# Analog_Temp_Ctrl.net
KiCad netlist of a schematic drawn in EAGLE
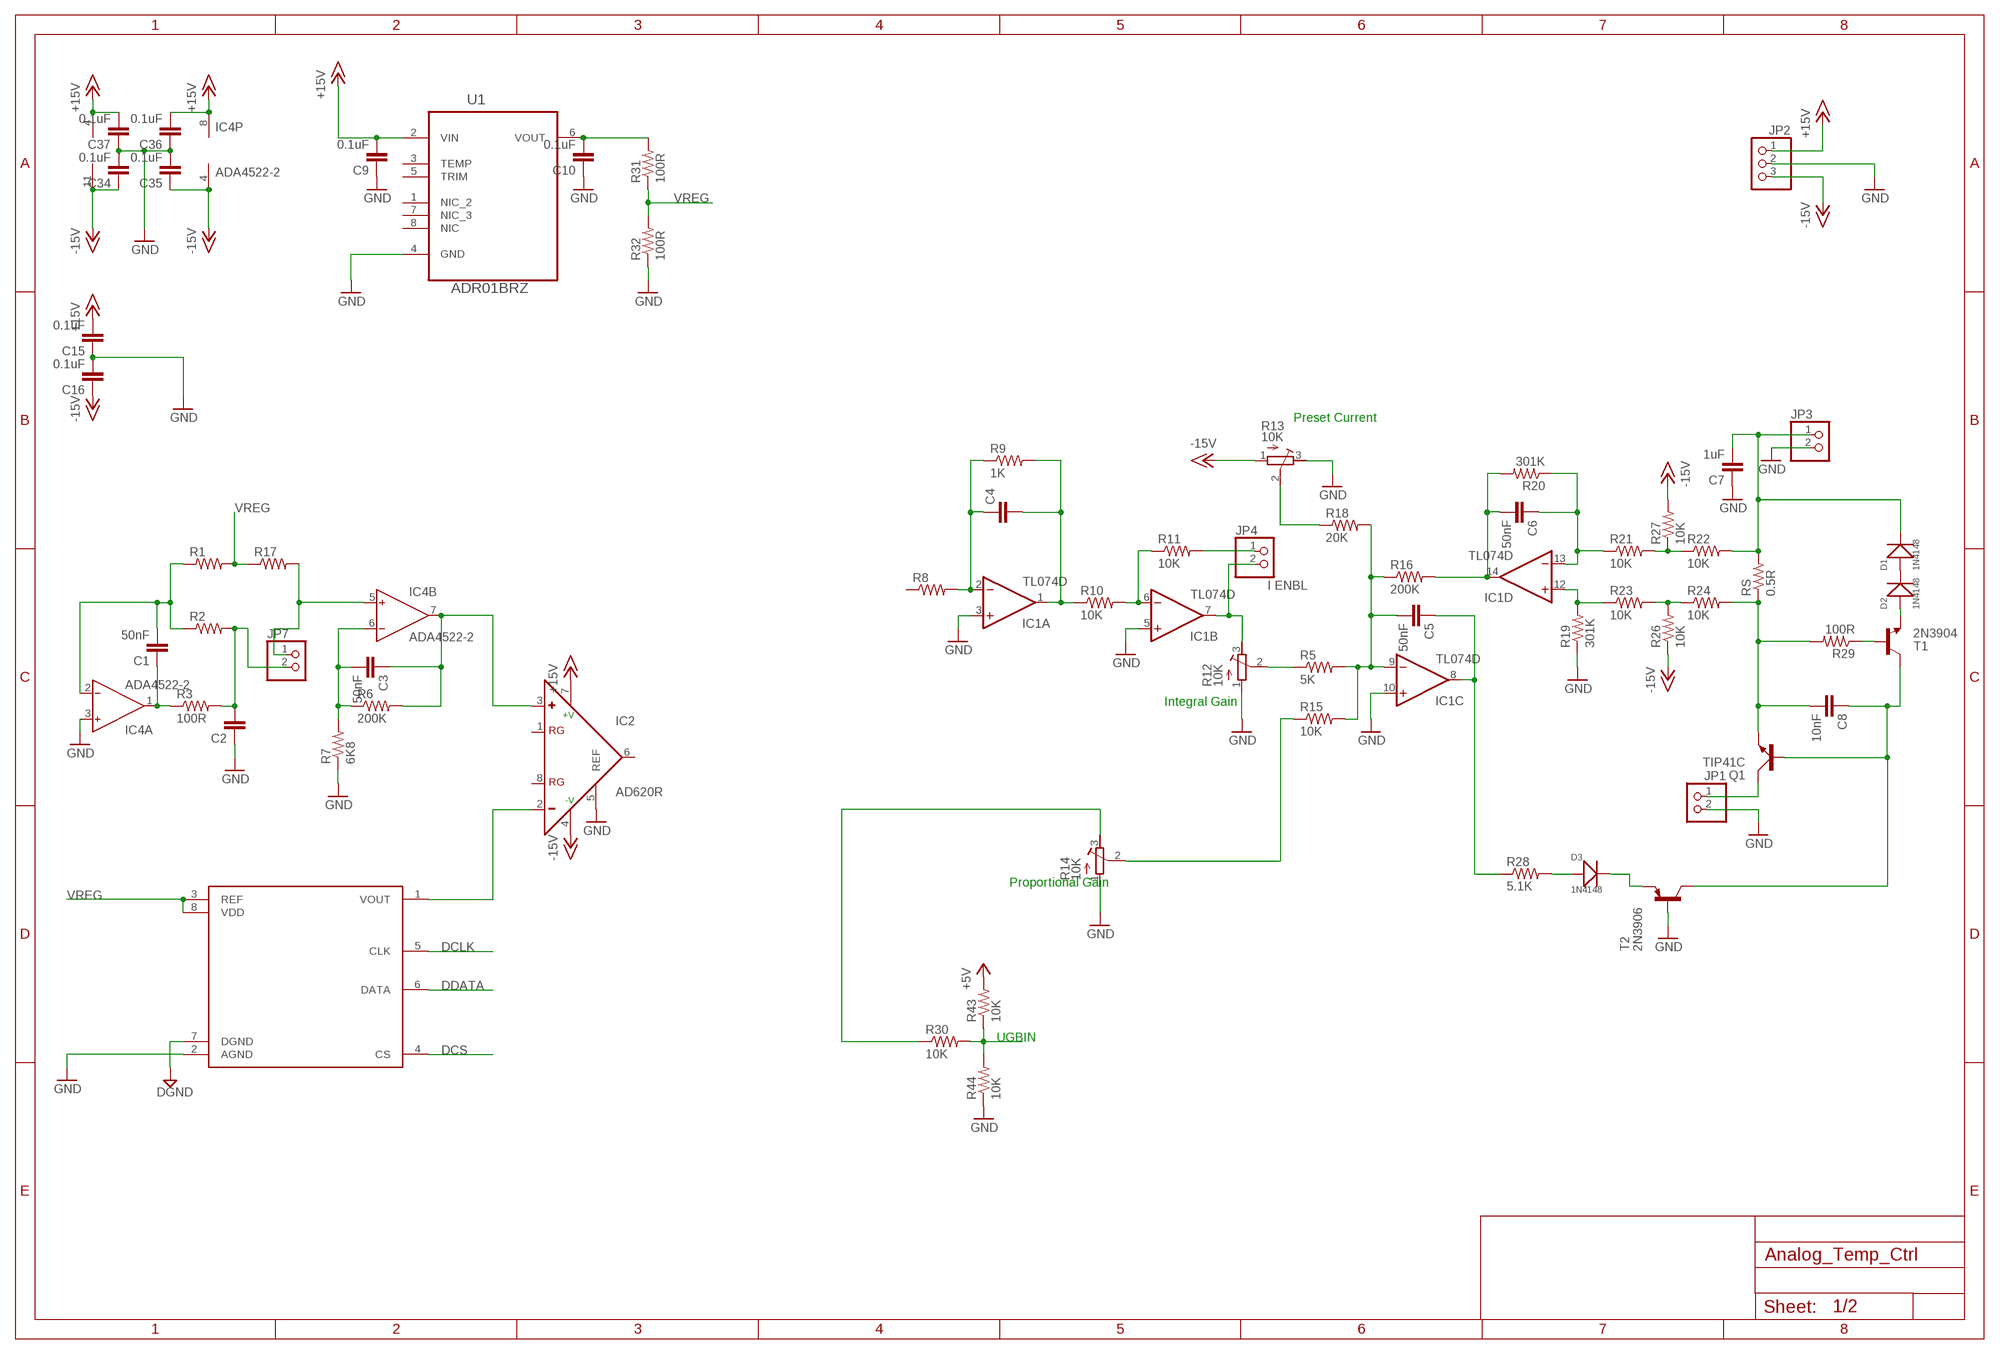
[diagram p0: schematic, sheet 1]
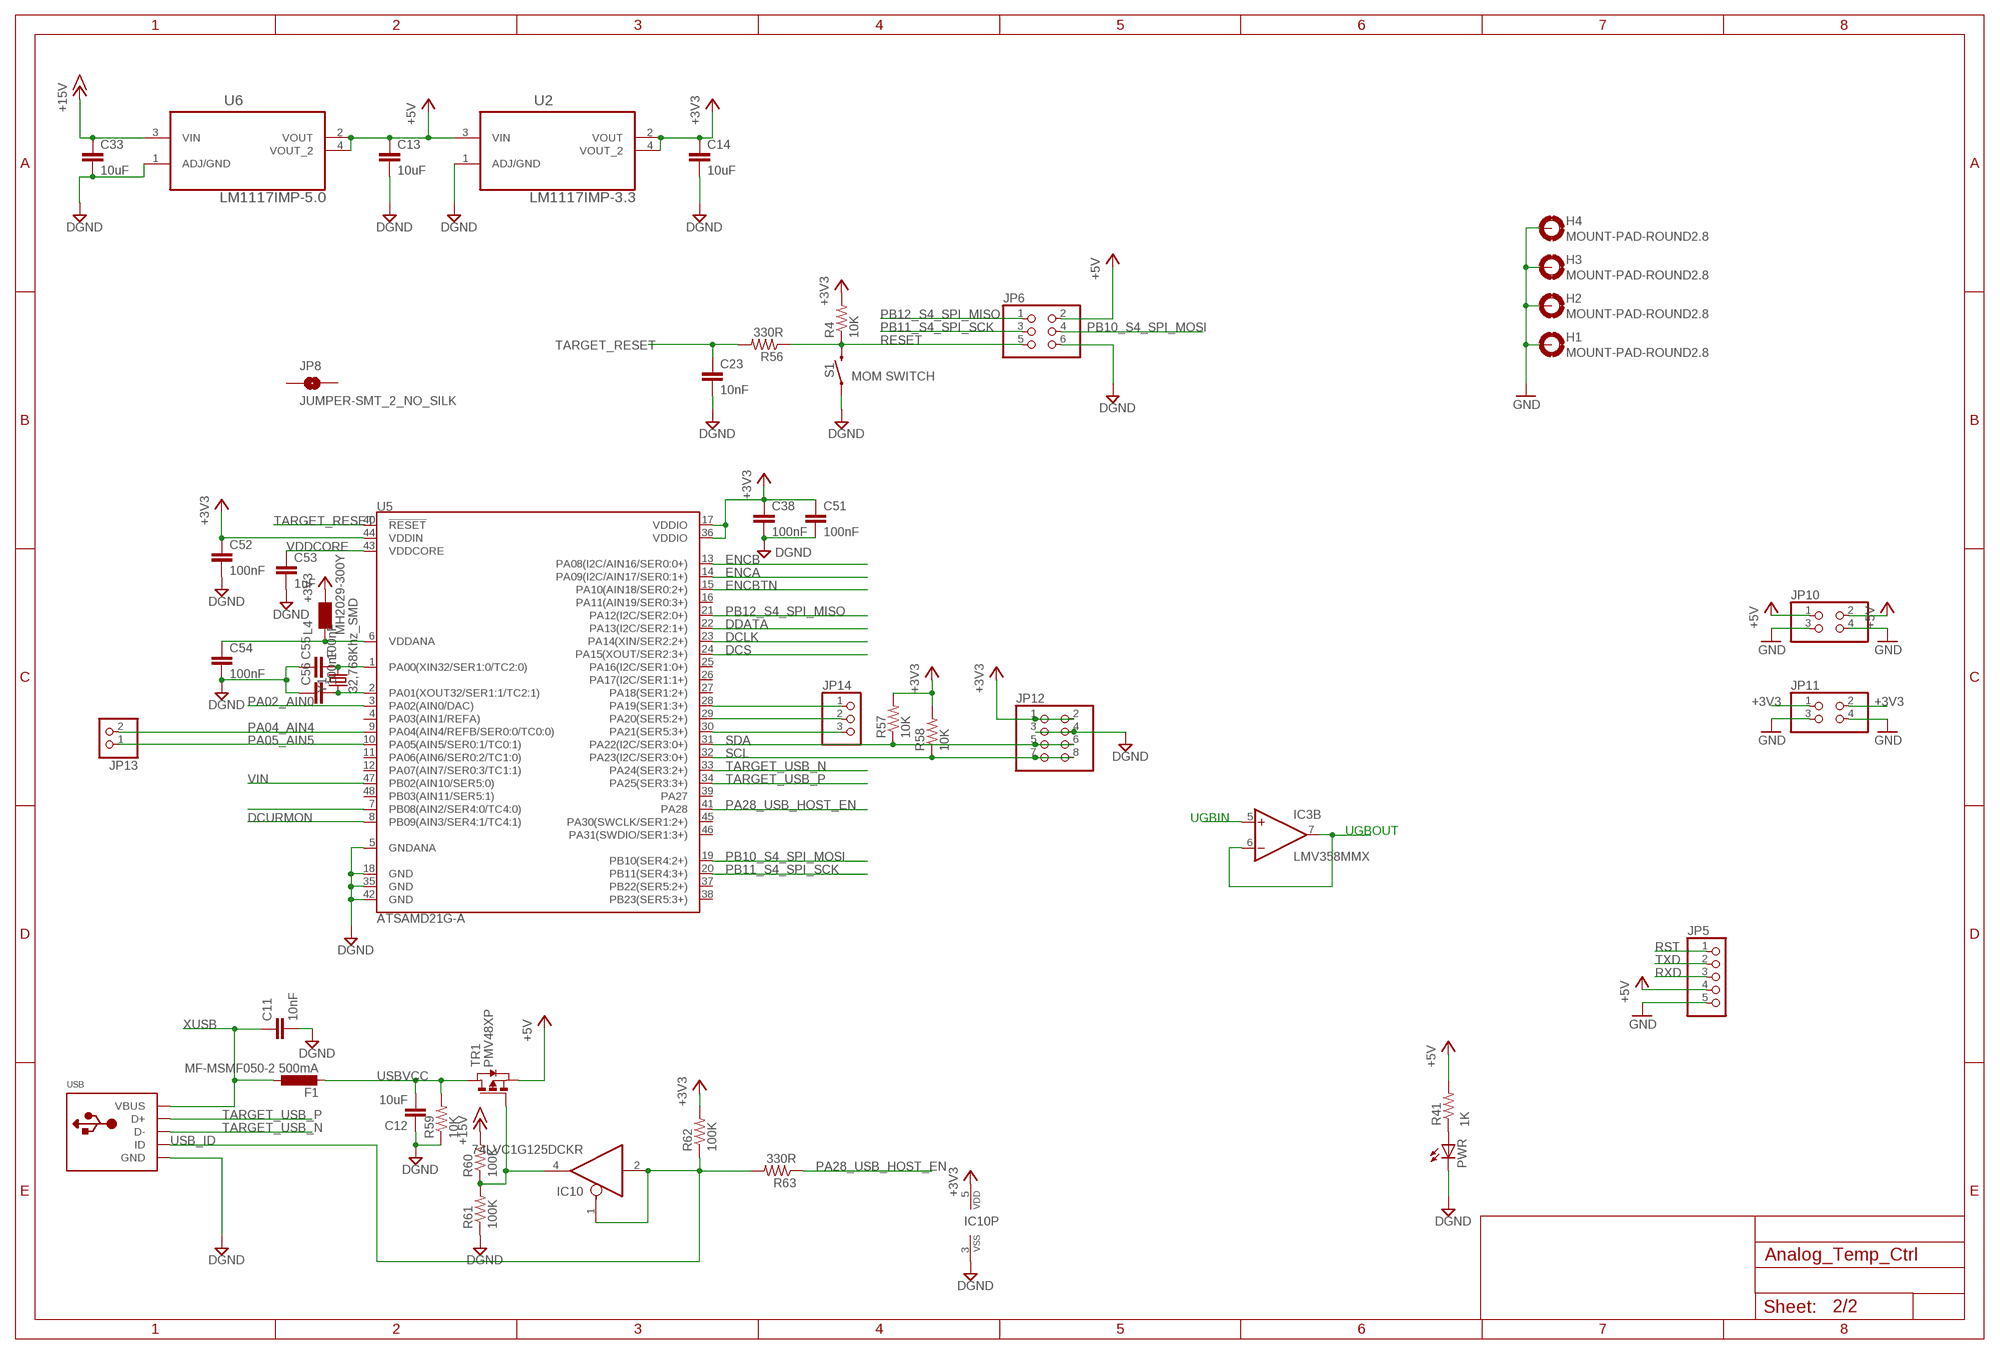
[diagram p1: schematic, sheet 2]

(export (version "E")
  (design (tool "Eeschema 10.0.6"))
  (components
    (comp (ref "C11")
      (value "10nF")
      (footprint "eagle-import:C0805")
      (libsource (lib "eagle-import") (part "C-EUC0805"))
    )
    (comp (ref "C12")
      (value "10uF")
      (footprint "eagle-import:C0805")
      (libsource (lib "eagle-import") (part "C-EUC0805"))
    )
    (comp (ref "C13")
      (value "10uF")
      (footprint "eagle-import:C0805")
      (libsource (lib "eagle-import") (part "C-EUC0805"))
    )
    (comp (ref "C14")
      (value "10uF")
      (footprint "eagle-import:C0805")
      (libsource (lib "eagle-import") (part "C-EUC0805"))
    )
    (comp (ref "C23")
      (value "10nF")
      (footprint "eagle-import:C0805")
      (libsource (lib "eagle-import") (part "C-EUC0805"))
    )
    (comp (ref "C33")
      (value "10uF")
      (footprint "eagle-import:C0805")
      (libsource (lib "eagle-import") (part "C-EUC0805"))
    )
    (comp (ref "C38")
      (value "100nF")
      (footprint "eagle-import:C0805")
      (libsource (lib "eagle-import") (part "C-EUC0805"))
    )
    (comp (ref "C51")
      (value "100nF")
      (footprint "eagle-import:C0805")
      (libsource (lib "eagle-import") (part "C-EUC0805"))
    )
    (comp (ref "C52")
      (value "100nF")
      (footprint "eagle-import:C0805")
      (libsource (lib "eagle-import") (part "C-EUC0805"))
    )
    (comp (ref "C53")
      (value "1uF")
      (footprint "eagle-import:C0805")
      (libsource (lib "eagle-import") (part "C-EUC0805"))
    )
    (comp (ref "C54")
      (value "100nF")
      (footprint "eagle-import:C0805")
      (libsource (lib "eagle-import") (part "C-EUC0805"))
    )
    (comp (ref "C55")
      (value "100nF")
      (footprint "eagle-import:C0805")
      (libsource (lib "eagle-import") (part "C-EUC0805"))
    )
    (comp (ref "C56")
      (value "100nF")
      (footprint "eagle-import:C0805")
      (libsource (lib "eagle-import") (part "C-EUC0805"))
    )
    (comp (ref "F1")
      (value "MF-MSMF050-2 500mA")
      (footprint "eagle-import:PROTEZIONE_L1812")
      (fields (field (name "PART_NUMBER") "MF-MSMF050-2"))
      (libsource (lib "eagle-import") (part "PROTEZIONE_0002_MF-MSMF050-2"))
    )
    (comp (ref "H1")
      (value "MOUNT-PAD-ROUND2.8")
      (footprint "eagle-import:2,8-PAD")
      (libsource (lib "eagle-import") (part "MOUNT-PAD-ROUND2.8"))
    )
    (comp (ref "H2")
      (value "MOUNT-PAD-ROUND2.8")
      (footprint "eagle-import:2,8-PAD")
      (libsource (lib "eagle-import") (part "MOUNT-PAD-ROUND2.8"))
    )
    (comp (ref "H3")
      (value "MOUNT-PAD-ROUND2.8")
      (footprint "eagle-import:2,8-PAD")
      (libsource (lib "eagle-import") (part "MOUNT-PAD-ROUND2.8"))
    )
    (comp (ref "H4")
      (value "MOUNT-PAD-ROUND2.8")
      (footprint "eagle-import:2,8-PAD")
      (libsource (lib "eagle-import") (part "MOUNT-PAD-ROUND2.8"))
    )
    (comp (ref "IC3")
      (value "LMV358MMX")
      (footprint "eagle-import:MSOP08")
      (libsource (lib "eagle-import") (part "LMV358?MMX"))
    )
    (comp (ref "IC10")
      (value "74LVC1G125DCKR")
      (footprint "eagle-import:INTEGRATEDCIRCUITS_SC70-5")
      (fields (field (name "PART_NUMBER") "SN74LVC1G125DCKR"))
      (libsource (lib "eagle-import") (part "INTEGRATEDCIRCUITS_0040_SN74LVC1G125DCKR"))
    )
    (comp (ref "JP5")
      (value "PINHD-1X5")
      (footprint "eagle-import:1X05")
      (libsource (lib "eagle-import") (part "PINHD-1X5"))
    )
    (comp (ref "JP6")
      (value "PINHD-2X3")
      (footprint "eagle-import:2X03")
      (libsource (lib "eagle-import") (part "PINHD-2X3"))
    )
    (comp (ref "JP8")
      (value "JUMPER-SMT_2_NO_SILK")
      (footprint "eagle-import:SMT-JUMPER_2_NO_SILK")
      (libsource (lib "eagle-import") (part "JUMPER-SMT_2_NO_SILK"))
    )
    (comp (ref "JP10")
      (value "PINHD-2X2")
      (footprint "eagle-import:2X02")
      (libsource (lib "eagle-import") (part "PINHD-2X2"))
    )
    (comp (ref "JP11")
      (value "PINHD-2X2")
      (footprint "eagle-import:2X02")
      (libsource (lib "eagle-import") (part "PINHD-2X2"))
    )
    (comp (ref "JP12")
      (value "PINHD-2X4")
      (footprint "eagle-import:2X04")
      (libsource (lib "eagle-import") (part "PINHD-2X4"))
    )
    (comp (ref "JP13")
      (value "PINHD-1X2")
      (footprint "eagle-import:1X02")
      (libsource (lib "eagle-import") (part "PINHD-1X2"))
    )
    (comp (ref "JP14")
      (value "PINHD-1X3")
      (footprint "eagle-import:1X03")
      (libsource (lib "eagle-import") (part "PINHD-1X3"))
    )
    (comp (ref "L4")
      (value "MH2029-300Y")
      (footprint "eagle-import:PROTEZIONE_0805")
      (fields (field (name "PART_NUMBER") "BLM21PG300SN1D_/_MH2029-300Y"))
      (libsource (lib "eagle-import") (part "PROTEZIONE_0001_BLM21PG300SN1D_/_MH2029-300Y"))
    )
    (comp (ref "PWR")
      (value "LEDCHIPLED_0805")
      (footprint "eagle-import:CHIPLED_0805")
      (libsource (lib "eagle-import") (part "LEDCHIPLED_0805"))
    )
    (comp (ref "R4")
      (value "10K")
      (footprint "eagle-import:R0805")
      (libsource (lib "eagle-import") (part "rcl_334_R-US_R0805"))
    )
    (comp (ref "R41")
      (value "1K")
      (footprint "eagle-import:R0805")
      (libsource (lib "eagle-import") (part "rcl_334_R-US_R0805"))
    )
    (comp (ref "R56")
      (value "330R")
      (footprint "eagle-import:R0805")
      (libsource (lib "eagle-import") (part "rcl_334_R-US_R0805"))
    )
    (comp (ref "R57")
      (value "10K")
      (footprint "eagle-import:R0805")
      (libsource (lib "eagle-import") (part "rcl_334_R-US_R0805"))
    )
    (comp (ref "R58")
      (value "10K")
      (footprint "eagle-import:R0805")
      (libsource (lib "eagle-import") (part "rcl_334_R-US_R0805"))
    )
    (comp (ref "R59")
      (value "10K")
      (footprint "eagle-import:R0805")
      (libsource (lib "eagle-import") (part "rcl_334_R-US_R0805"))
    )
    (comp (ref "R60")
      (value "100K")
      (footprint "eagle-import:R0805")
      (libsource (lib "eagle-import") (part "rcl_334_R-US_R0805"))
    )
    (comp (ref "R61")
      (value "100K")
      (footprint "eagle-import:R0805")
      (libsource (lib "eagle-import") (part "rcl_334_R-US_R0805"))
    )
    (comp (ref "R62")
      (value "100K")
      (footprint "eagle-import:R0805")
      (libsource (lib "eagle-import") (part "rcl_334_R-US_R0805"))
    )
    (comp (ref "R63")
      (value "330R")
      (footprint "eagle-import:R0805")
      (libsource (lib "eagle-import") (part "rcl_334_R-US_R0805"))
    )
    (comp (ref "S1")
      (value "MOM SWITCH")
      (footprint "eagle-import:TACTILE_SWITCH_SMD_5.2MM")
      (libsource (lib "eagle-import") (part "MOMENTARY-SWITCH-SPST-SMD-5.2MM"))
    )
    (comp (ref "TR1")
      (value "PMV48XP")
      (footprint "eagle-import:TRANSISTORS_SOT-23")
      (libsource (lib "eagle-import") (part "TRANSISTORS_0297_PMV48XP"))
    )
    (comp (ref "U2")
      (value "LM1117IMP-3.3")
      (footprint "eagle-import:SOT230P696X180-4N")
      (libsource (lib "eagle-import") (part "LM1117IMP-3.3"))
    )
    (comp (ref "U5")
      (value "ATSAMD21G-A")
      (footprint "eagle-import:TQFP-48")
      (libsource (lib "eagle-import") (part "ATSAMD21G-A"))
    )
    (comp (ref "U6")
      (value "LM1117IMP-5.0")
      (footprint "eagle-import:SOT230P696X180-4N")
      (libsource (lib "eagle-import") (part "LM1117IMP-5.0"))
    )
    (comp (ref "USB")
      (value "USBMINIB")
      (footprint "eagle-import:USB-MINIB")
      (libsource (lib "eagle-import") (part "USBMINIB"))
    )
    (comp (ref "Y1")
      (value "32,768Khz_SMD")
      (footprint "eagle-import:CRISTALLI_RESONATOR_EPSON_FC_145")
      (fields (field (name "PART_NUMBER") "ABS07-32.768KHZ-T"))
      (libsource (lib "eagle-import") (part "CRISTALLI_0213_ABS07-32.768KHZ-T"))
    )
    (comp (ref "C1")
      (value "50nF")
      (footprint "eagle-import:C0805")
      (libsource (lib "eagle-import") (part "C-EUC0805"))
    )
    (comp (ref "C2")
      (value "C-EUC0805")
      (footprint "eagle-import:C0805")
      (libsource (lib "eagle-import") (part "C-EUC0805"))
    )
    (comp (ref "C3")
      (value "50nF")
      (footprint "eagle-import:C0805")
      (libsource (lib "eagle-import") (part "C-EUC0805"))
    )
    (comp (ref "C4")
      (value "C-EUC0805")
      (footprint "eagle-import:C0805")
      (libsource (lib "eagle-import") (part "C-EUC0805"))
    )
    (comp (ref "C5")
      (value "50nF")
      (footprint "eagle-import:C0805")
      (libsource (lib "eagle-import") (part "C-EUC0805"))
    )
    (comp (ref "C6")
      (value "50nF")
      (footprint "eagle-import:C0805")
      (libsource (lib "eagle-import") (part "C-EUC0805"))
    )
    (comp (ref "C7")
      (value "1uF")
      (footprint "eagle-import:C0805")
      (libsource (lib "eagle-import") (part "C-EUC0805"))
    )
    (comp (ref "C8")
      (value "10nF")
      (footprint "eagle-import:C0805")
      (libsource (lib "eagle-import") (part "C-EUC0805"))
    )
    (comp (ref "C9")
      (value "0.1uF")
      (footprint "eagle-import:C0805")
      (libsource (lib "eagle-import") (part "C-EUC0805"))
    )
    (comp (ref "C10")
      (value "0.1uF")
      (footprint "eagle-import:C0805")
      (libsource (lib "eagle-import") (part "C-EUC0805"))
    )
    (comp (ref "C15")
      (value "0.1uF")
      (footprint "eagle-import:C0805")
      (libsource (lib "eagle-import") (part "C-EUC0805"))
    )
    (comp (ref "C16")
      (value "0.1uF")
      (footprint "eagle-import:C0805")
      (libsource (lib "eagle-import") (part "C-EUC0805"))
    )
    (comp (ref "C34")
      (value "0.1uF")
      (footprint "eagle-import:C0805")
      (libsource (lib "eagle-import") (part "C-EUC0805"))
    )
    (comp (ref "C35")
      (value "0.1uF")
      (footprint "eagle-import:C0805")
      (libsource (lib "eagle-import") (part "C-EUC0805"))
    )
    (comp (ref "C36")
      (value "0.1uF")
      (footprint "eagle-import:C0805")
      (libsource (lib "eagle-import") (part "C-EUC0805"))
    )
    (comp (ref "C37")
      (value "0.1uF")
      (footprint "eagle-import:C0805")
      (libsource (lib "eagle-import") (part "C-EUC0805"))
    )
    (comp (ref "D1")
      (value "1N4148")
      (footprint "eagle-import:LL-34")
      (libsource (lib "eagle-import") (part "SMD-DIODE-SWITCH-1N4148(LL-34)"))
    )
    (comp (ref "D2")
      (value "1N4148")
      (footprint "eagle-import:LL-34")
      (libsource (lib "eagle-import") (part "SMD-DIODE-SWITCH-1N4148(LL-34)"))
    )
    (comp (ref "D3")
      (value "1N4148")
      (footprint "eagle-import:LL-34")
      (libsource (lib "eagle-import") (part "SMD-DIODE-SWITCH-1N4148(LL-34)"))
    )
    (comp (ref "IC1")
      (value "TL074D")
      (footprint "eagle-import:SO14")
      (libsource (lib "eagle-import") (part "TL074D"))
    )
    (comp (ref "IC2")
      (value "AD620R")
      (footprint "eagle-import:SO8")
      (fields (field (name "MPN") "AD620AR"))
      (libsource (lib "eagle-import") (part "AD620R"))
    )
    (comp (ref "IC4")
      (value "ADA4522-2")
      (footprint "eagle-import:SO8")
      (fields (field (name "MPN") "AD8599ARZ"))
      (libsource (lib "eagle-import") (part "AD8599R"))
    )
    (comp (ref "JP1")
      (value "PINHD-1X2/90")
      (footprint "eagle-import:1X02_90")
      (libsource (lib "eagle-import") (part "PINHD-1X2/90"))
    )
    (comp (ref "JP2")
      (value "PINHD-1X3/90")
      (footprint "eagle-import:1X03_90")
      (libsource (lib "eagle-import") (part "PINHD-1X3/90"))
    )
    (comp (ref "JP3")
      (value "PINHD-1X2/90")
      (footprint "eagle-import:1X02_90")
      (libsource (lib "eagle-import") (part "PINHD-1X2/90"))
    )
    (comp (ref "JP4")
      (value "PINHD-1X2")
      (footprint "eagle-import:1X02")
      (libsource (lib "eagle-import") (part "PINHD-1X2"))
    )
    (comp (ref "JP7")
      (value "PINHD-1X2")
      (footprint "eagle-import:1X02")
      (libsource (lib "eagle-import") (part "PINHD-1X2"))
    )
    (comp (ref "Q1")
      (value "TIP41C")
      (footprint "eagle-import:TO220AV")
      (libsource (lib "eagle-import") (part "TIP41C"))
    )
    (comp (ref "R1")
      (value "R-US_R0805")
      (footprint "eagle-import:R0805")
      (libsource (lib "eagle-import") (part "rcl_334_R-US_R0805"))
    )
    (comp (ref "R2")
      (value "R-US_R0805")
      (footprint "eagle-import:R0805")
      (libsource (lib "eagle-import") (part "rcl_334_R-US_R0805"))
    )
    (comp (ref "R3")
      (value "100R")
      (footprint "eagle-import:R0805")
      (libsource (lib "eagle-import") (part "rcl_334_R-US_R0805"))
    )
    (comp (ref "R5")
      (value "5K")
      (footprint "eagle-import:R0805")
      (libsource (lib "eagle-import") (part "rcl_334_R-US_R0805"))
    )
    (comp (ref "R6")
      (value "200K")
      (footprint "eagle-import:R0805")
      (libsource (lib "eagle-import") (part "rcl_334_R-US_R0805"))
    )
    (comp (ref "R7")
      (value "6K8")
      (footprint "eagle-import:R0805")
      (libsource (lib "eagle-import") (part "rcl_334_R-US_R0805"))
    )
    (comp (ref "R8")
      (value "R-US_R0805")
      (footprint "eagle-import:R0805")
      (libsource (lib "eagle-import") (part "rcl_334_R-US_R0805"))
    )
    (comp (ref "R9")
      (value "1K")
      (footprint "eagle-import:R0805")
      (libsource (lib "eagle-import") (part "rcl_334_R-US_R0805"))
    )
    (comp (ref "R10")
      (value "10K")
      (footprint "eagle-import:R0805")
      (libsource (lib "eagle-import") (part "rcl_334_R-US_R0805"))
    )
    (comp (ref "R11")
      (value "10K")
      (footprint "eagle-import:R0805")
      (libsource (lib "eagle-import") (part "rcl_334_R-US_R0805"))
    )
    (comp (ref "R12")
      (value "10K")
      (footprint "eagle-import:RTRIM3296W")
      (libsource (lib "eagle-import") (part "R-TRIMM3296W"))
    )
    (comp (ref "R13")
      (value "10K")
      (footprint "eagle-import:RTRIM3296W")
      (libsource (lib "eagle-import") (part "R-TRIMM3296W"))
    )
    (comp (ref "R14")
      (value "10K")
      (footprint "eagle-import:RTRIM3296W")
      (libsource (lib "eagle-import") (part "R-TRIMM3296W"))
    )
    (comp (ref "R15")
      (value "10K")
      (footprint "eagle-import:R0805")
      (libsource (lib "eagle-import") (part "rcl_334_R-US_R0805"))
    )
    (comp (ref "R16")
      (value "200K")
      (footprint "eagle-import:R0805")
      (libsource (lib "eagle-import") (part "rcl_334_R-US_R0805"))
    )
    (comp (ref "R17")
      (value "R-US_R0805")
      (footprint "eagle-import:R0805")
      (libsource (lib "eagle-import") (part "rcl_334_R-US_R0805"))
    )
    (comp (ref "R18")
      (value "20K")
      (footprint "eagle-import:R0805")
      (libsource (lib "eagle-import") (part "rcl_334_R-US_R0805"))
    )
    (comp (ref "R19")
      (value "301K")
      (footprint "eagle-import:R0805")
      (libsource (lib "eagle-import") (part "rcl_334_R-US_R0805"))
    )
    (comp (ref "R20")
      (value "301K")
      (footprint "eagle-import:R0805")
      (libsource (lib "eagle-import") (part "rcl_334_R-US_R0805"))
    )
    (comp (ref "R21")
      (value "10K")
      (footprint "eagle-import:R0805")
      (libsource (lib "eagle-import") (part "rcl_334_R-US_R0805"))
    )
    (comp (ref "R22")
      (value "10K")
      (footprint "eagle-import:R0805")
      (libsource (lib "eagle-import") (part "rcl_334_R-US_R0805"))
    )
    (comp (ref "R23")
      (value "10K")
      (footprint "eagle-import:R0805")
      (libsource (lib "eagle-import") (part "rcl_334_R-US_R0805"))
    )
    (comp (ref "R24")
      (value "10K")
      (footprint "eagle-import:R0805")
      (libsource (lib "eagle-import") (part "rcl_334_R-US_R0805"))
    )
    (comp (ref "R26")
      (value "10K")
      (footprint "eagle-import:R0805")
      (libsource (lib "eagle-import") (part "rcl_334_R-US_R0805"))
    )
    (comp (ref "R27")
      (value "10K")
      (footprint "eagle-import:R0805")
      (libsource (lib "eagle-import") (part "rcl_334_R-US_R0805"))
    )
    (comp (ref "R28")
      (value "5.1K")
      (footprint "eagle-import:R0805")
      (libsource (lib "eagle-import") (part "rcl_334_R-US_R0805"))
    )
    (comp (ref "R29")
      (value "100R")
      (footprint "eagle-import:R0805")
      (libsource (lib "eagle-import") (part "rcl_334_R-US_R0805"))
    )
    (comp (ref "R30")
      (value "10K")
      (footprint "eagle-import:R0805")
      (libsource (lib "eagle-import") (part "rcl_334_R-US_R0805"))
    )
    (comp (ref "R31")
      (value "100R")
      (footprint "eagle-import:R0805")
      (libsource (lib "eagle-import") (part "rcl_334_R-US_R0805"))
    )
    (comp (ref "R32")
      (value "100R")
      (footprint "eagle-import:R0805")
      (libsource (lib "eagle-import") (part "rcl_334_R-US_R0805"))
    )
    (comp (ref "R43")
      (value "10K")
      (footprint "eagle-import:R0805")
      (libsource (lib "eagle-import") (part "rcl_334_R-US_R0805"))
    )
    (comp (ref "R44")
      (value "10K")
      (footprint "eagle-import:R0805")
      (libsource (lib "eagle-import") (part "rcl_334_R-US_R0805"))
    )
    (comp (ref "RS")
      (value "0.5R")
      (footprint "eagle-import:R2512")
      (libsource (lib "eagle-import") (part "R-US_R2512"))
    )
    (comp (ref "T1")
      (value "2N3904")
      (footprint "eagle-import:SOT23-BEC")
      (libsource (lib "eagle-import") (part "-NPN-SOT23-BECMMBT3904LT1"))
    )
    (comp (ref "T2")
      (value "2N3906")
      (footprint "eagle-import:SOT23-BEC")
      (libsource (lib "eagle-import") (part "-PNP-SOT23-BECMMBT3906LT1"))
    )
    (comp (ref "U1")
      (value "ADR01BRZ")
      (footprint "eagle-import:SOIC127P600X175-8N")
      (libsource (lib "eagle-import") (part "ADR01BRZ"))
    )
    (comp (ref "U3")
      (value "AD5541")
      (footprint "eagle-import:SOIC-8")
      (libsource (lib "eagle-import") (part "AD5541"))
    )
  )
  (nets
    (net (code "1") (name "+3V3") (class "Default")
      (node (ref "C14") (pin "1") (pinfunction "1_1") (pintype "passive"))
      (node (ref "C38") (pin "1") (pinfunction "1_1") (pintype "passive"))
      (node (ref "C51") (pin "1") (pinfunction "1_1") (pintype "passive"))
      (node (ref "C52") (pin "1") (pinfunction "1_1") (pintype "passive"))
      (node (ref "IC10") (pin "5") (pinfunction "VDD_5") (pintype "power_in"))
      (node (ref "JP12") (pin "1") (pinfunction "1_1") (pintype "passive"))
      (node (ref "JP12") (pin "2") (pinfunction "2_2") (pintype "passive"))
      (node (ref "L4") (pin "2") (pinfunction "2_2") (pintype "passive"))
      (node (ref "R4") (pin "2") (pinfunction "2_2") (pintype "passive"))
      (node (ref "R57") (pin "2") (pinfunction "2_2") (pintype "passive"))
      (node (ref "R58") (pin "2") (pinfunction "2_2") (pintype "passive"))
      (node (ref "R62") (pin "2") (pinfunction "2_2") (pintype "passive"))
      (node (ref "U2") (pin "2") (pinfunction "VOUT_2") (pintype "output"))
      (node (ref "U2") (pin "4") (pinfunction "VOUT_2_4") (pintype "output"))
      (node (ref "U5") (pin "17") (pinfunction "VDDIO_17") (pintype "bidirectional"))
      (node (ref "U5") (pin "36") (pinfunction "VDDIO_36") (pintype "bidirectional"))
      (node (ref "U5") (pin "44") (pinfunction "VDDIN_44") (pintype "bidirectional"))
    )
    (net (code "2") (name "+5V") (class "Default")
      (node (ref "C13") (pin "1") (pinfunction "1_1") (pintype "passive"))
      (node (ref "JP10") (pin "1") (pinfunction "1_1") (pintype "passive"))
      (node (ref "JP10") (pin "2") (pinfunction "2_2") (pintype "passive"))
      (node (ref "JP5") (pin "4") (pinfunction "4_4") (pintype "passive"))
      (node (ref "JP6") (pin "2") (pinfunction "2_2") (pintype "passive"))
      (node (ref "R41") (pin "2") (pinfunction "2_2") (pintype "passive"))
      (node (ref "R43") (pin "2") (pinfunction "2_2") (pintype "passive"))
      (node (ref "TR1") (pin "2") (pinfunction "S_2") (pintype "passive"))
      (node (ref "U2") (pin "3") (pinfunction "VIN_3") (pintype "input"))
      (node (ref "U6") (pin "2") (pinfunction "VOUT_2") (pintype "output"))
      (node (ref "U6") (pin "4") (pinfunction "VOUT_2_4") (pintype "output"))
    )
    (net (code "3") (name "+15V") (class "Default")
      (node (ref "C15") (pin "2") (pinfunction "2_2") (pintype "passive"))
      (node (ref "C33") (pin "1") (pinfunction "1_1") (pintype "passive"))
      (node (ref "C36") (pin "2") (pinfunction "2_2") (pintype "passive"))
      (node (ref "C37") (pin "2") (pinfunction "2_2") (pintype "passive"))
      (node (ref "C9") (pin "2") (pinfunction "2_2") (pintype "passive"))
      (node (ref "IC1") (pin "4") (pinfunction "V+_4") (pintype "power_in"))
      (node (ref "IC2") (pin "7") (pinfunction "+V_7") (pintype "power_in"))
      (node (ref "IC4") (pin "8") (pinfunction "V+_8") (pintype "power_in"))
      (node (ref "JP2") (pin "1") (pinfunction "1_1") (pintype "passive"))
      (node (ref "R60") (pin "2") (pinfunction "2_2") (pintype "passive"))
      (node (ref "U1") (pin "2") (pinfunction "VIN_2") (pintype "input"))
      (node (ref "U6") (pin "3") (pinfunction "VIN_3") (pintype "input"))
    )
    (net (code "4") (name "-15V") (class "Default")
      (node (ref "C16") (pin "1") (pinfunction "1_1") (pintype "passive"))
      (node (ref "C34") (pin "1") (pinfunction "1_1") (pintype "passive"))
      (node (ref "C35") (pin "1") (pinfunction "1_1") (pintype "passive"))
      (node (ref "IC1") (pin "11") (pinfunction "V-_11") (pintype "power_in"))
      (node (ref "IC2") (pin "4") (pinfunction "-V_4") (pintype "power_in"))
      (node (ref "IC4") (pin "4") (pinfunction "V-_4") (pintype "power_in"))
      (node (ref "JP2") (pin "3") (pinfunction "3_3") (pintype "passive"))
      (node (ref "R13") (pin "1") (pinfunction "A_1") (pintype "passive"))
      (node (ref "R26") (pin "1") (pinfunction "1_1") (pintype "passive"))
      (node (ref "R27") (pin "2") (pinfunction "2_2") (pintype "passive"))
    )
    (net (code "5") (name "3V3") (class "Default")
      (node (ref "JP11") (pin "1") (pinfunction "1_1") (pintype "passive"))
      (node (ref "JP11") (pin "2") (pinfunction "2_2") (pintype "passive"))
    )
    (net (code "6") (name "DCLK") (class "Default")
      (node (ref "U3") (pin "5") (pinfunction "CLK_5") (pintype "bidirectional"))
      (node (ref "U5") (pin "23") (pinfunction "PA14(XIN/SER2:2+)_23") (pintype "bidirectional"))
    )
    (net (code "7") (name "DCS") (class "Default")
      (node (ref "U3") (pin "4") (pinfunction "CS_4") (pintype "bidirectional"))
      (node (ref "U5") (pin "24") (pinfunction "PA15(XOUT/SER2:3+)_24") (pintype "bidirectional"))
    )
    (net (code "8") (name "DCURMON") (class "Default")
      (node (ref "U5") (pin "8") (pinfunction "PB09(AIN3/SER4:1/TC4:1)_8") (pintype "bidirectional"))
    )
    (net (code "9") (name "DDATA") (class "Default")
      (node (ref "U3") (pin "6") (pinfunction "DATA_6") (pintype "bidirectional"))
      (node (ref "U5") (pin "22") (pinfunction "PA13(I2C/SER2:1+)_22") (pintype "bidirectional"))
    )
    (net (code "10") (name "DGND") (class "Default")
      (node (ref "C11") (pin "2") (pinfunction "2_2") (pintype "passive"))
      (node (ref "C12") (pin "1") (pinfunction "1_1") (pintype "passive"))
      (node (ref "C13") (pin "2") (pinfunction "2_2") (pintype "passive"))
      (node (ref "C14") (pin "2") (pinfunction "2_2") (pintype "passive"))
      (node (ref "C23") (pin "2") (pinfunction "2_2") (pintype "passive"))
      (node (ref "C33") (pin "2") (pinfunction "2_2") (pintype "passive"))
      (node (ref "C38") (pin "2") (pinfunction "2_2") (pintype "passive"))
      (node (ref "C51") (pin "2") (pinfunction "2_2") (pintype "passive"))
      (node (ref "C52") (pin "2") (pinfunction "2_2") (pintype "passive"))
      (node (ref "C53") (pin "2") (pinfunction "2_2") (pintype "passive"))
      (node (ref "C54") (pin "2") (pinfunction "2_2") (pintype "passive"))
      (node (ref "C55") (pin "1") (pinfunction "1_1") (pintype "passive"))
      (node (ref "C56") (pin "1") (pinfunction "1_1") (pintype "passive"))
      (node (ref "IC10") (pin "3") (pinfunction "VSS_3") (pintype "power_in"))
      (node (ref "JP12") (pin "3") (pinfunction "3_3") (pintype "passive"))
      (node (ref "JP12") (pin "4") (pinfunction "4_4") (pintype "passive"))
      (node (ref "JP6") (pin "6") (pinfunction "6_6") (pintype "passive"))
      (node (ref "PWR") (pin "C") (pinfunction "C_C") (pintype "passive"))
      (node (ref "R59") (pin "1") (pinfunction "1_1") (pintype "passive"))
      (node (ref "R61") (pin "1") (pinfunction "1_1") (pintype "passive"))
      (node (ref "S1") (pin "1") (pinfunction "1_1") (pintype "passive"))
      (node (ref "U2") (pin "1") (pinfunction "ADJ/GND_1") (pintype "passive"))
      (node (ref "U3") (pin "7") (pinfunction "DGND_7") (pintype "bidirectional"))
      (node (ref "U5") (pin "18") (pinfunction "GND_18") (pintype "bidirectional"))
      (node (ref "U5") (pin "35") (pinfunction "GND_35") (pintype "bidirectional"))
      (node (ref "U5") (pin "42") (pinfunction "GND_42") (pintype "bidirectional"))
      (node (ref "U5") (pin "5") (pinfunction "GNDANA_5") (pintype "bidirectional"))
      (node (ref "U6") (pin "1") (pinfunction "ADJ/GND_1") (pintype "passive"))
      (node (ref "USB") (pin "GND") (pinfunction "GND_GND") (pintype "power_in"))
    )
    (net (code "11") (name "ENCA") (class "Default")
      (node (ref "U5") (pin "14") (pinfunction "PA09(I2C/AIN17/SER0:1+)_14") (pintype "bidirectional"))
    )
    (net (code "12") (name "ENCB") (class "Default")
      (node (ref "U5") (pin "13") (pinfunction "PA08(I2C/AIN16/SER0:0+)_13") (pintype "bidirectional"))
    )
    (net (code "13") (name "ENCBTN") (class "Default")
      (node (ref "U5") (pin "15") (pinfunction "PA10(AIN18/SER0:2+)_15") (pintype "bidirectional"))
    )
    (net (code "14") (name "GND") (class "Default")
      (node (ref "C10") (pin "1") (pinfunction "1_1") (pintype "passive"))
      (node (ref "C15") (pin "1") (pinfunction "1_1") (pintype "passive"))
      (node (ref "C16") (pin "2") (pinfunction "2_2") (pintype "passive"))
      (node (ref "C2") (pin "1") (pinfunction "1_1") (pintype "passive"))
      (node (ref "C34") (pin "2") (pinfunction "2_2") (pintype "passive"))
      (node (ref "C35") (pin "2") (pinfunction "2_2") (pintype "passive"))
      (node (ref "C36") (pin "1") (pinfunction "1_1") (pintype "passive"))
      (node (ref "C37") (pin "1") (pinfunction "1_1") (pintype "passive"))
      (node (ref "C7") (pin "1") (pinfunction "1_1") (pintype "passive"))
      (node (ref "C9") (pin "1") (pinfunction "1_1") (pintype "passive"))
      (node (ref "H1") (pin "B2,8") (pinfunction "MOUNT_B2,8") (pintype "passive"))
      (node (ref "H2") (pin "B2,8") (pinfunction "MOUNT_B2,8") (pintype "passive"))
      (node (ref "H3") (pin "B2,8") (pinfunction "MOUNT_B2,8") (pintype "passive"))
      (node (ref "H4") (pin "B2,8") (pinfunction "MOUNT_B2,8") (pintype "passive"))
      (node (ref "IC1") (pin "10") (pinfunction "+IN_10") (pintype "input"))
      (node (ref "IC1") (pin "3") (pinfunction "+IN_3") (pintype "input"))
      (node (ref "IC1") (pin "5") (pinfunction "+IN_5") (pintype "input"))
      (node (ref "IC2") (pin "5") (pinfunction "REF_5") (pintype "passive"))
      (node (ref "IC4") (pin "3") (pinfunction "IN+_3") (pintype "input"))
      (node (ref "JP1") (pin "2") (pinfunction "2_2") (pintype "passive"))
      (node (ref "JP10") (pin "3") (pinfunction "3_3") (pintype "passive"))
      (node (ref "JP10") (pin "4") (pinfunction "4_4") (pintype "passive"))
      (node (ref "JP11") (pin "3") (pinfunction "3_3") (pintype "passive"))
      (node (ref "JP11") (pin "4") (pinfunction "4_4") (pintype "passive"))
      (node (ref "JP2") (pin "2") (pinfunction "2_2") (pintype "passive"))
      (node (ref "JP3") (pin "2") (pinfunction "2_2") (pintype "passive"))
      (node (ref "JP5") (pin "5") (pinfunction "5_5") (pintype "passive"))
      (node (ref "R12") (pin "1") (pinfunction "A_1") (pintype "passive"))
      (node (ref "R13") (pin "3") (pinfunction "E_3") (pintype "passive"))
      (node (ref "R14") (pin "1") (pinfunction "A_1") (pintype "passive"))
      (node (ref "R19") (pin "1") (pinfunction "1_1") (pintype "passive"))
      (node (ref "R32") (pin "1") (pinfunction "1_1") (pintype "passive"))
      (node (ref "R44") (pin "1") (pinfunction "1_1") (pintype "passive"))
      (node (ref "R7") (pin "1") (pinfunction "1_1") (pintype "passive"))
      (node (ref "T2") (pin "B") (pinfunction "B_B") (pintype "passive"))
      (node (ref "U1") (pin "4") (pinfunction "GND_4") (pintype "passive"))
      (node (ref "U3") (pin "2") (pinfunction "AGND_2") (pintype "bidirectional"))
    )
    (net (code "15") (name "Net-(C2-Pad2)") (class "Default")
      (node (ref "C2") (pin "2") (pinfunction "2_2") (pintype "passive"))
      (node (ref "JP7") (pin "2") (pinfunction "2_2") (pintype "passive"))
      (node (ref "R2") (pin "2") (pinfunction "2_2") (pintype "passive"))
      (node (ref "R3") (pin "2") (pinfunction "2_2") (pintype "passive"))
    )
    (net (code "16") (name "Net-(C8-Pad1)") (class "Default")
      (node (ref "C8") (pin "1") (pinfunction "1_1") (pintype "passive"))
      (node (ref "Q1") (pin "B") (pinfunction "B_B") (pintype "passive"))
      (node (ref "T1") (pin "C") (pinfunction "C_C") (pintype "passive"))
      (node (ref "T2") (pin "C") (pinfunction "C_C") (pintype "passive"))
    )
    (net (code "17") (name "Net-(C8-Pad2)") (class "Default")
      (node (ref "C8") (pin "2") (pinfunction "2_2") (pintype "passive"))
      (node (ref "Q1") (pin "E") (pinfunction "E_E") (pintype "passive"))
      (node (ref "R24") (pin "2") (pinfunction "2_2") (pintype "passive"))
      (node (ref "R29") (pin "2") (pinfunction "2_2") (pintype "passive"))
      (node (ref "RS") (pin "1") (pinfunction "1_1") (pintype "passive"))
    )
    (net (code "18") (name "Net-(D1-+)") (class "Default")
      (node (ref "D1") (pin "A") (pinfunction "+_A") (pintype "passive"))
      (node (ref "D2") (pin "C") (pinfunction "-_C") (pintype "passive"))
    )
    (net (code "19") (name "Net-(D1--)") (class "Default")
      (node (ref "C7") (pin "2") (pinfunction "2_2") (pintype "passive"))
      (node (ref "D1") (pin "C") (pinfunction "-_C") (pintype "passive"))
      (node (ref "JP3") (pin "1") (pinfunction "1_1") (pintype "passive"))
      (node (ref "R22") (pin "2") (pinfunction "2_2") (pintype "passive"))
      (node (ref "RS") (pin "2") (pinfunction "2_2") (pintype "passive"))
    )
    (net (code "20") (name "Net-(D2-+)") (class "Default")
      (node (ref "D2") (pin "A") (pinfunction "+_A") (pintype "passive"))
      (node (ref "T1") (pin "E") (pinfunction "E_E") (pintype "passive"))
    )
    (net (code "21") (name "Net-(D3-+)") (class "Default")
      (node (ref "D3") (pin "A") (pinfunction "+_A") (pintype "passive"))
      (node (ref "R28") (pin "2") (pinfunction "2_2") (pintype "passive"))
    )
    (net (code "22") (name "Net-(D3--)") (class "Default")
      (node (ref "D3") (pin "C") (pinfunction "-_C") (pintype "passive"))
      (node (ref "T2") (pin "E") (pinfunction "E_E") (pintype "passive"))
    )
    (net (code "23") (name "Net-(IC1A--IN)") (class "Default")
      (node (ref "C4") (pin "1") (pinfunction "1_1") (pintype "passive"))
      (node (ref "IC1") (pin "2") (pinfunction "-IN_2") (pintype "input"))
      (node (ref "R8") (pin "2") (pinfunction "2_2") (pintype "passive"))
      (node (ref "R9") (pin "1") (pinfunction "1_1") (pintype "passive"))
    )
    (net (code "24") (name "Net-(IC1A-OUT)") (class "Default")
      (node (ref "C4") (pin "2") (pinfunction "2_2") (pintype "passive"))
      (node (ref "IC1") (pin "1") (pinfunction "OUT_1") (pintype "output"))
      (node (ref "R10") (pin "1") (pinfunction "1_1") (pintype "passive"))
      (node (ref "R9") (pin "2") (pinfunction "2_2") (pintype "passive"))
    )
    (net (code "25") (name "Net-(IC1B--IN)") (class "Default")
      (node (ref "IC1") (pin "6") (pinfunction "-IN_6") (pintype "input"))
      (node (ref "R10") (pin "2") (pinfunction "2_2") (pintype "passive"))
      (node (ref "R11") (pin "1") (pinfunction "1_1") (pintype "passive"))
    )
    (net (code "26") (name "Net-(IC1B-OUT)") (class "Default")
      (node (ref "IC1") (pin "7") (pinfunction "OUT_7") (pintype "output"))
      (node (ref "JP4") (pin "2") (pinfunction "2_2") (pintype "passive"))
      (node (ref "R12") (pin "3") (pinfunction "E_3") (pintype "passive"))
    )
    (net (code "27") (name "Net-(IC1C--IN)") (class "Default")
      (node (ref "C5") (pin "2") (pinfunction "2_2") (pintype "passive"))
      (node (ref "IC1") (pin "9") (pinfunction "-IN_9") (pintype "input"))
      (node (ref "R15") (pin "2") (pinfunction "2_2") (pintype "passive"))
      (node (ref "R16") (pin "1") (pinfunction "1_1") (pintype "passive"))
      (node (ref "R18") (pin "2") (pinfunction "2_2") (pintype "passive"))
      (node (ref "R5") (pin "2") (pinfunction "2_2") (pintype "passive"))
    )
    (net (code "28") (name "Net-(IC1C-OUT)") (class "Default")
      (node (ref "C5") (pin "1") (pinfunction "1_1") (pintype "passive"))
      (node (ref "IC1") (pin "8") (pinfunction "OUT_8") (pintype "output"))
      (node (ref "R28") (pin "1") (pinfunction "1_1") (pintype "passive"))
    )
    (net (code "29") (name "Net-(IC1D-+IN)") (class "Default")
      (node (ref "IC1") (pin "12") (pinfunction "+IN_12") (pintype "input"))
      (node (ref "R19") (pin "2") (pinfunction "2_2") (pintype "passive"))
      (node (ref "R23") (pin "1") (pinfunction "1_1") (pintype "passive"))
    )
    (net (code "30") (name "Net-(IC1D--IN)") (class "Default")
      (node (ref "C6") (pin "1") (pinfunction "1_1") (pintype "passive"))
      (node (ref "IC1") (pin "13") (pinfunction "-IN_13") (pintype "input"))
      (node (ref "R20") (pin "1") (pinfunction "1_1") (pintype "passive"))
      (node (ref "R21") (pin "1") (pinfunction "1_1") (pintype "passive"))
    )
    (net (code "31") (name "Net-(IC1D-OUT)") (class "Default")
      (node (ref "C6") (pin "2") (pinfunction "2_2") (pintype "passive"))
      (node (ref "IC1") (pin "14") (pinfunction "OUT_14") (pintype "output"))
      (node (ref "R16") (pin "2") (pinfunction "2_2") (pintype "passive"))
      (node (ref "R20") (pin "2") (pinfunction "2_2") (pintype "passive"))
    )
    (net (code "32") (name "Net-(IC2-+)") (class "Default")
      (node (ref "C3") (pin "1") (pinfunction "1_1") (pintype "passive"))
      (node (ref "IC2") (pin "3") (pinfunction "+_3") (pintype "input"))
      (node (ref "IC4") (pin "7") (pinfunction "OUT_7") (pintype "output"))
      (node (ref "R6") (pin "2") (pinfunction "2_2") (pintype "passive"))
    )
    (net (code "33") (name "Net-(IC2--)") (class "Default")
      (node (ref "IC2") (pin "2") (pinfunction "-_2") (pintype "input"))
      (node (ref "U3") (pin "1") (pinfunction "VOUT_1") (pintype "bidirectional"))
    )
    (net (code "34") (name "Net-(IC3B--IN)") (class "Default")
      (node (ref "IC3") (pin "6") (pinfunction "-IN_6") (pintype "input"))
      (node (ref "IC3") (pin "7") (pinfunction "OUT_7") (pintype "output"))
    )
    (net (code "35") (name "Net-(IC4A-IN-)") (class "Default")
      (node (ref "C1") (pin "2") (pinfunction "2_2") (pintype "passive"))
      (node (ref "IC4") (pin "2") (pinfunction "IN-_2") (pintype "input"))
      (node (ref "R1") (pin "1") (pinfunction "1_1") (pintype "passive"))
      (node (ref "R2") (pin "1") (pinfunction "1_1") (pintype "passive"))
    )
    (net (code "36") (name "Net-(IC4A-OUT)") (class "Default")
      (node (ref "C1") (pin "1") (pinfunction "1_1") (pintype "passive"))
      (node (ref "IC4") (pin "1") (pinfunction "OUT_1") (pintype "output"))
      (node (ref "R3") (pin "1") (pinfunction "1_1") (pintype "passive"))
    )
    (net (code "37") (name "Net-(IC4B-IN+)") (class "Default")
      (node (ref "IC4") (pin "5") (pinfunction "IN+_5") (pintype "input"))
      (node (ref "JP7") (pin "1") (pinfunction "1_1") (pintype "passive"))
      (node (ref "R17") (pin "2") (pinfunction "2_2") (pintype "passive"))
    )
    (net (code "38") (name "Net-(IC4B-IN-)") (class "Default")
      (node (ref "C3") (pin "2") (pinfunction "2_2") (pintype "passive"))
      (node (ref "IC4") (pin "6") (pinfunction "IN-_6") (pintype "input"))
      (node (ref "R6") (pin "1") (pinfunction "1_1") (pintype "passive"))
      (node (ref "R7") (pin "2") (pinfunction "2_2") (pintype "passive"))
    )
    (net (code "39") (name "Net-(IC10A-O)") (class "Default")
      (node (ref "IC10") (pin "4") (pinfunction "O_4") (pintype "tri_state"))
      (node (ref "R60") (pin "1") (pinfunction "1_1") (pintype "passive"))
      (node (ref "R61") (pin "2") (pinfunction "2_2") (pintype "passive"))
      (node (ref "TR1") (pin "3") (pinfunction "G_3") (pintype "passive"))
    )
    (net (code "40") (name "Net-(JP1-Pad1)") (class "Default")
      (node (ref "JP1") (pin "1") (pinfunction "1_1") (pintype "passive"))
      (node (ref "Q1") (pin "C") (pinfunction "C_C") (pintype "passive"))
    )
    (net (code "41") (name "Net-(JP4-Pad1)") (class "Default")
      (node (ref "JP4") (pin "1") (pinfunction "1_1") (pintype "passive"))
      (node (ref "R11") (pin "2") (pinfunction "2_2") (pintype "passive"))
    )
    (net (code "42") (name "Net-(PWR-PadA)") (class "Default")
      (node (ref "PWR") (pin "A") (pinfunction "A_A") (pintype "passive"))
      (node (ref "R41") (pin "1") (pinfunction "1_1") (pintype "passive"))
    )
    (net (code "43") (name "Net-(R12-S)") (class "Default")
      (node (ref "R12") (pin "2") (pinfunction "S_2") (pintype "passive"))
      (node (ref "R5") (pin "1") (pinfunction "1_1") (pintype "passive"))
    )
    (net (code "44") (name "Net-(R13-S)") (class "Default")
      (node (ref "R13") (pin "2") (pinfunction "S_2") (pintype "passive"))
      (node (ref "R18") (pin "1") (pinfunction "1_1") (pintype "passive"))
    )
    (net (code "45") (name "Net-(R14-E)") (class "Default")
      (node (ref "R14") (pin "3") (pinfunction "E_3") (pintype "passive"))
      (node (ref "R30") (pin "1") (pinfunction "1_1") (pintype "passive"))
    )
    (net (code "46") (name "Net-(R14-S)") (class "Default")
      (node (ref "R14") (pin "2") (pinfunction "S_2") (pintype "passive"))
      (node (ref "R15") (pin "1") (pinfunction "1_1") (pintype "passive"))
    )
    (net (code "47") (name "Net-(R21-Pad2)") (class "Default")
      (node (ref "R21") (pin "2") (pinfunction "2_2") (pintype "passive"))
      (node (ref "R22") (pin "1") (pinfunction "1_1") (pintype "passive"))
      (node (ref "R27") (pin "1") (pinfunction "1_1") (pintype "passive"))
    )
    (net (code "48") (name "Net-(R23-Pad2)") (class "Default")
      (node (ref "R23") (pin "2") (pinfunction "2_2") (pintype "passive"))
      (node (ref "R24") (pin "1") (pinfunction "1_1") (pintype "passive"))
      (node (ref "R26") (pin "2") (pinfunction "2_2") (pintype "passive"))
    )
    (net (code "49") (name "Net-(R29-Pad1)") (class "Default")
      (node (ref "R29") (pin "1") (pinfunction "1_1") (pintype "passive"))
      (node (ref "T1") (pin "B") (pinfunction "B_B") (pintype "passive"))
    )
    (net (code "50") (name "Net-(U1-VOUT)") (class "Default")
      (node (ref "C10") (pin "2") (pinfunction "2_2") (pintype "passive"))
      (node (ref "R31") (pin "2") (pinfunction "2_2") (pintype "passive"))
      (node (ref "U1") (pin "6") (pinfunction "VOUT_6") (pintype "output"))
    )
    (net (code "51") (name "Net-(U5-PA00(XIN32{slash}SER1:0{slash}TC2:0))") (class "Default")
      (node (ref "C55") (pin "2") (pinfunction "2_2") (pintype "passive"))
      (node (ref "U5") (pin "1") (pinfunction "PA00(XIN32/SER1:0/TC2:0)_1") (pintype "bidirectional"))
      (node (ref "Y1") (pin "P$2") (pinfunction "2_P$2") (pintype "bidirectional"))
    )
    (net (code "52") (name "Net-(U5-PA01(XOUT32{slash}SER1:1{slash}TC2:1))") (class "Default")
      (node (ref "C56") (pin "2") (pinfunction "2_2") (pintype "passive"))
      (node (ref "U5") (pin "2") (pinfunction "PA01(XOUT32/SER1:1/TC2:1)_2") (pintype "bidirectional"))
      (node (ref "Y1") (pin "P$1") (pinfunction "1_P$1") (pintype "bidirectional"))
    )
    (net (code "53") (name "Net-(U5-PA19(SER1:3+))") (class "Default")
      (node (ref "JP14") (pin "1") (pinfunction "1_1") (pintype "passive"))
      (node (ref "U5") (pin "28") (pinfunction "PA19(SER1:3+)_28") (pintype "bidirectional"))
    )
    (net (code "54") (name "Net-(U5-PA20(SER5:2+))") (class "Default")
      (node (ref "JP14") (pin "2") (pinfunction "2_2") (pintype "passive"))
      (node (ref "U5") (pin "29") (pinfunction "PA20(SER5:2+)_29") (pintype "bidirectional"))
    )
    (net (code "55") (name "Net-(U5-PA21(SER5:3+))") (class "Default")
      (node (ref "JP14") (pin "3") (pinfunction "3_3") (pintype "passive"))
      (node (ref "U5") (pin "30") (pinfunction "PA21(SER5:3+)_30") (pintype "bidirectional"))
    )
    (net (code "56") (name "Net-(U5-VDDANA)") (class "Default")
      (node (ref "C54") (pin "1") (pinfunction "1_1") (pintype "passive"))
      (node (ref "L4") (pin "1") (pinfunction "1_1") (pintype "passive"))
      (node (ref "U5") (pin "6") (pinfunction "VDDANA_6") (pintype "bidirectional"))
    )
    (net (code "57") (name "PA02_AIN0") (class "Default")
      (node (ref "U5") (pin "3") (pinfunction "PA02(AIN0/DAC)_3") (pintype "bidirectional"))
    )
    (net (code "58") (name "PA04_AIN4") (class "Default")
      (node (ref "JP13") (pin "2") (pinfunction "2_2") (pintype "passive"))
      (node (ref "U5") (pin "9") (pinfunction "PA04(AIN4/REFB/SER0:0/TC0:0)_9") (pintype "bidirectional"))
    )
    (net (code "59") (name "PA05_AIN5") (class "Default")
      (node (ref "JP13") (pin "1") (pinfunction "1_1") (pintype "passive"))
      (node (ref "U5") (pin "10") (pinfunction "PA05(AIN5/SER0:1/TC0:1)_10") (pintype "bidirectional"))
    )
    (net (code "60") (name "PA28_USB_HOST_EN") (class "Default")
      (node (ref "R63") (pin "1") (pinfunction "1_1") (pintype "passive"))
      (node (ref "U5") (pin "41") (pinfunction "PA28_41") (pintype "bidirectional"))
    )
    (net (code "61") (name "PB10_S4_SPI_MOSI") (class "Default")
      (node (ref "JP6") (pin "4") (pinfunction "4_4") (pintype "passive"))
      (node (ref "U5") (pin "19") (pinfunction "PB10(SER4:2+)_19") (pintype "bidirectional"))
    )
    (net (code "62") (name "PB11_S4_SPI_SCK") (class "Default")
      (node (ref "JP6") (pin "3") (pinfunction "3_3") (pintype "passive"))
      (node (ref "U5") (pin "20") (pinfunction "PB11(SER4:3+)_20") (pintype "bidirectional"))
    )
    (net (code "63") (name "PB12_S4_SPI_MISO") (class "Default")
      (node (ref "JP6") (pin "1") (pinfunction "1_1") (pintype "passive"))
      (node (ref "U5") (pin "21") (pinfunction "PA12(I2C/SER2:0+)_21") (pintype "bidirectional"))
    )
    (net (code "64") (name "RESET") (class "Default")
      (node (ref "JP6") (pin "5") (pinfunction "5_5") (pintype "passive"))
      (node (ref "R4") (pin "1") (pinfunction "1_1") (pintype "passive"))
      (node (ref "R56") (pin "1") (pinfunction "1_1") (pintype "passive"))
      (node (ref "S1") (pin "3") (pinfunction "2_3") (pintype "passive"))
    )
    (net (code "65") (name "SCL") (class "Default")
      (node (ref "JP12") (pin "7") (pinfunction "7_7") (pintype "passive"))
      (node (ref "JP12") (pin "8") (pinfunction "8_8") (pintype "passive"))
      (node (ref "R58") (pin "1") (pinfunction "1_1") (pintype "passive"))
      (node (ref "U5") (pin "32") (pinfunction "PA23(I2C/SER3:0+)_32") (pintype "bidirectional"))
    )
    (net (code "66") (name "SDA") (class "Default")
      (node (ref "JP12") (pin "5") (pinfunction "5_5") (pintype "passive"))
      (node (ref "JP12") (pin "6") (pinfunction "6_6") (pintype "passive"))
      (node (ref "R57") (pin "1") (pinfunction "1_1") (pintype "passive"))
      (node (ref "U5") (pin "31") (pinfunction "PA22(I2C/SER3:0+)_31") (pintype "bidirectional"))
    )
    (net (code "67") (name "TARGET_RESET") (class "Default")
      (node (ref "C23") (pin "1") (pinfunction "1_1") (pintype "passive"))
      (node (ref "R56") (pin "2") (pinfunction "2_2") (pintype "passive"))
      (node (ref "U5") (pin "40") (pinfunction "~{RESET}_40") (pintype "bidirectional"))
    )
    (net (code "68") (name "TARGET_USB_N") (class "Default")
      (node (ref "U5") (pin "33") (pinfunction "PA24(SER3:2+)_33") (pintype "bidirectional"))
      (node (ref "USB") (pin "D-") (pinfunction "D-_D-") (pintype "bidirectional"))
    )
    (net (code "69") (name "TARGET_USB_P") (class "Default")
      (node (ref "U5") (pin "34") (pinfunction "PA25(SER3:3+)_34") (pintype "bidirectional"))
      (node (ref "USB") (pin "D+") (pinfunction "D+_D+") (pintype "bidirectional"))
    )
    (net (code "70") (name "UGBIN") (class "Default")
      (node (ref "IC3") (pin "5") (pinfunction "+IN_5") (pintype "input"))
      (node (ref "R30") (pin "2") (pinfunction "2_2") (pintype "passive"))
      (node (ref "R43") (pin "1") (pinfunction "1_1") (pintype "passive"))
      (node (ref "R44") (pin "2") (pinfunction "2_2") (pintype "passive"))
    )
    (net (code "71") (name "USBVCC") (class "Default")
      (node (ref "C12") (pin "2") (pinfunction "2_2") (pintype "passive"))
      (node (ref "F1") (pin "2") (pinfunction "2_2") (pintype "passive"))
      (node (ref "R59") (pin "2") (pinfunction "2_2") (pintype "passive"))
      (node (ref "TR1") (pin "1") (pinfunction "D_1") (pintype "passive"))
    )
    (net (code "72") (name "USB_ID") (class "Default")
      (node (ref "IC10") (pin "1") (pinfunction "OE_1") (pintype "input"))
      (node (ref "IC10") (pin "2") (pinfunction "I_2") (pintype "input"))
      (node (ref "R62") (pin "1") (pinfunction "1_1") (pintype "passive"))
      (node (ref "R63") (pin "2") (pinfunction "2_2") (pintype "passive"))
      (node (ref "USB") (pin "ID") (pinfunction "ID_ID") (pintype "bidirectional"))
    )
    (net (code "73") (name "VDDCORE") (class "Default")
      (node (ref "C53") (pin "1") (pinfunction "1_1") (pintype "passive"))
      (node (ref "U5") (pin "43") (pinfunction "VDDCORE_43") (pintype "bidirectional"))
    )
    (net (code "74") (name "VIN") (class "Default")
      (node (ref "U5") (pin "47") (pinfunction "PB02(AIN10/SER5:0)_47") (pintype "bidirectional"))
    )
    (net (code "75") (name "VREG") (class "Default")
      (node (ref "R1") (pin "2") (pinfunction "2_2") (pintype "passive"))
      (node (ref "R17") (pin "1") (pinfunction "1_1") (pintype "passive"))
      (node (ref "R31") (pin "1") (pinfunction "1_1") (pintype "passive"))
      (node (ref "R32") (pin "2") (pinfunction "2_2") (pintype "passive"))
      (node (ref "U3") (pin "3") (pinfunction "REF_3") (pintype "bidirectional"))
      (node (ref "U3") (pin "8") (pinfunction "VDD_8") (pintype "bidirectional"))
    )
    (net (code "76") (name "XUSB") (class "Default")
      (node (ref "C11") (pin "1") (pinfunction "1_1") (pintype "passive"))
      (node (ref "F1") (pin "1") (pinfunction "1_1") (pintype "passive"))
      (node (ref "USB") (pin "VBUS") (pinfunction "VBUS_VBUS") (pintype "power_in"))
    )
    (net (code "77") (name "unconnected-(IC2-OUT-Pad6)") (class "Default")
      (node (ref "IC2") (pin "6") (pinfunction "OUT_6") (pintype "output"))
    )
    (net (code "78") (name "unconnected-(IC2-RG-Pad1)") (class "Default")
      (node (ref "IC2") (pin "1") (pinfunction "RG_1") (pintype "passive"))
    )
    (net (code "79") (name "unconnected-(IC2-RG-Pad8)") (class "Default")
      (node (ref "IC2") (pin "8") (pinfunction "RG_8") (pintype "passive"))
    )
    (net (code "80") (name "unconnected-(JP5-Pad1)") (class "Default")
      (node (ref "JP5") (pin "1") (pinfunction "1_1") (pintype "passive"))
    )
    (net (code "81") (name "unconnected-(JP5-Pad2)") (class "Default")
      (node (ref "JP5") (pin "2") (pinfunction "2_2") (pintype "passive"))
    )
    (net (code "82") (name "unconnected-(JP5-Pad3)") (class "Default")
      (node (ref "JP5") (pin "3") (pinfunction "3_3") (pintype "passive"))
    )
    (net (code "83") (name "unconnected-(JP8-Pad1)") (class "Default")
      (node (ref "JP8") (pin "1") (pinfunction "1_1") (pintype "passive"))
    )
    (net (code "84") (name "unconnected-(JP8-Pad2)") (class "Default")
      (node (ref "JP8") (pin "2") (pinfunction "2_2") (pintype "passive"))
    )
    (net (code "85") (name "unconnected-(R8-Pad1)") (class "Default")
      (node (ref "R8") (pin "1") (pinfunction "1_1") (pintype "passive"))
    )
    (net (code "86") (name "unconnected-(U1-NIC-Pad8)") (class "Default")
      (node (ref "U1") (pin "8") (pinfunction "NIC_8") (pintype "no_connect"))
    )
    (net (code "87") (name "unconnected-(U1-NIC_2-Pad1)") (class "Default")
      (node (ref "U1") (pin "1") (pinfunction "NIC_2_1") (pintype "no_connect"))
    )
    (net (code "88") (name "unconnected-(U1-NIC_3-Pad7)") (class "Default")
      (node (ref "U1") (pin "7") (pinfunction "NIC_3_7") (pintype "no_connect"))
    )
    (net (code "89") (name "unconnected-(U1-TEMP-Pad3)") (class "Default")
      (node (ref "U1") (pin "3") (pinfunction "TEMP_3") (pintype "passive"))
    )
    (net (code "90") (name "unconnected-(U1-TRIM-Pad5)") (class "Default")
      (node (ref "U1") (pin "5") (pinfunction "TRIM_5") (pintype "passive"))
    )
    (net (code "91") (name "unconnected-(U5-PA03(AIN1{slash}REFA)-Pad4)") (class "Default")
      (node (ref "U5") (pin "4") (pinfunction "PA03(AIN1/REFA)_4") (pintype "bidirectional"))
    )
    (net (code "92") (name "unconnected-(U5-PA06(AIN6{slash}SER0:2{slash}TC1:0)-Pad11)") (class "Default")
      (node (ref "U5") (pin "11") (pinfunction "PA06(AIN6/SER0:2/TC1:0)_11") (pintype "bidirectional"))
    )
    (net (code "93") (name "unconnected-(U5-PA07(AIN7{slash}SER0:3{slash}TC1:1)-Pad12)") (class "Default")
      (node (ref "U5") (pin "12") (pinfunction "PA07(AIN7/SER0:3/TC1:1)_12") (pintype "bidirectional"))
    )
    (net (code "94") (name "unconnected-(U5-PA11(AIN19{slash}SER0:3+)-Pad16)") (class "Default")
      (node (ref "U5") (pin "16") (pinfunction "PA11(AIN19/SER0:3+)_16") (pintype "bidirectional"))
    )
    (net (code "95") (name "unconnected-(U5-PA16(I2C{slash}SER1:0+)-Pad25)") (class "Default")
      (node (ref "U5") (pin "25") (pinfunction "PA16(I2C/SER1:0+)_25") (pintype "bidirectional"))
    )
    (net (code "96") (name "unconnected-(U5-PA17(I2C{slash}SER1:1+)-Pad26)") (class "Default")
      (node (ref "U5") (pin "26") (pinfunction "PA17(I2C/SER1:1+)_26") (pintype "bidirectional"))
    )
    (net (code "97") (name "unconnected-(U5-PA18(SER1:2+)-Pad27)") (class "Default")
      (node (ref "U5") (pin "27") (pinfunction "PA18(SER1:2+)_27") (pintype "bidirectional"))
    )
    (net (code "98") (name "unconnected-(U5-PA27-Pad39)") (class "Default")
      (node (ref "U5") (pin "39") (pinfunction "PA27_39") (pintype "bidirectional"))
    )
    (net (code "99") (name "unconnected-(U5-PA30(SWCLK{slash}SER1:2+)-Pad45)") (class "Default")
      (node (ref "U5") (pin "45") (pinfunction "PA30(SWCLK/SER1:2+)_45") (pintype "bidirectional"))
    )
    (net (code "100") (name "unconnected-(U5-PA31(SWDIO{slash}SER1:3+)-Pad46)") (class "Default")
      (node (ref "U5") (pin "46") (pinfunction "PA31(SWDIO/SER1:3+)_46") (pintype "bidirectional"))
    )
    (net (code "101") (name "unconnected-(U5-PB03(AIN11{slash}SER5:1)-Pad48)") (class "Default")
      (node (ref "U5") (pin "48") (pinfunction "PB03(AIN11/SER5:1)_48") (pintype "bidirectional"))
    )
    (net (code "102") (name "unconnected-(U5-PB08(AIN2{slash}SER4:0{slash}TC4:0)-Pad7)") (class "Default")
      (node (ref "U5") (pin "7") (pinfunction "PB08(AIN2/SER4:0/TC4:0)_7") (pintype "bidirectional"))
    )
    (net (code "103") (name "unconnected-(U5-PB22(SER5:2+)-Pad37)") (class "Default")
      (node (ref "U5") (pin "37") (pinfunction "PB22(SER5:2+)_37") (pintype "bidirectional"))
    )
    (net (code "104") (name "unconnected-(U5-PB23(SER5:3+)-Pad38)") (class "Default")
      (node (ref "U5") (pin "38") (pinfunction "PB23(SER5:3+)_38") (pintype "bidirectional"))
    )
  )
)
